# P07_SHARED_SENSORS.net
KiCad netlist of a schematic drawn in EasyEDA
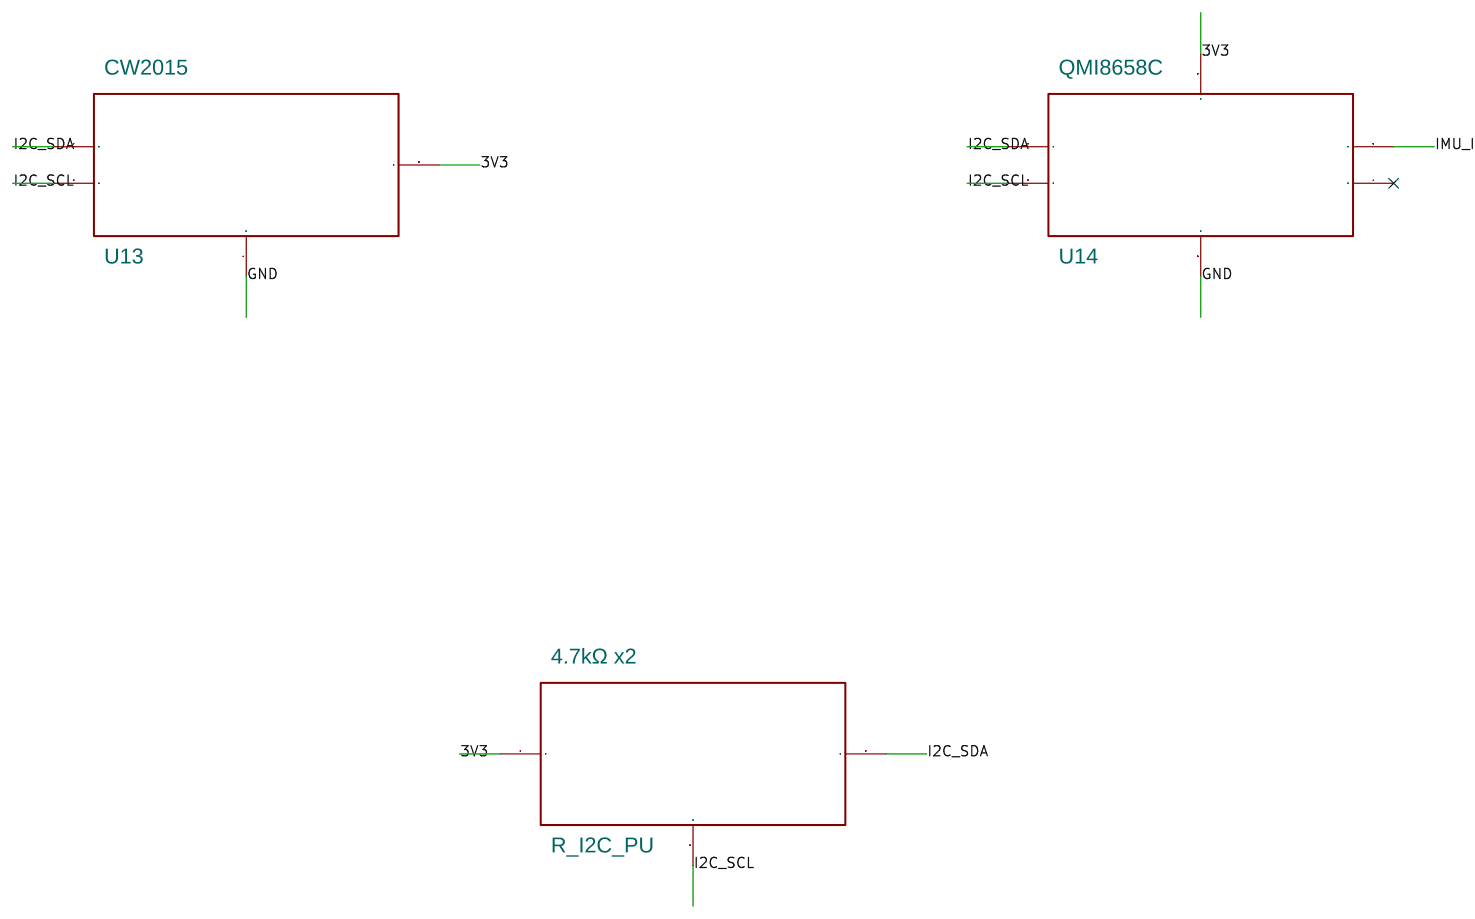
[diagram p0: schematic sheet]

(export (version "E")
  (design (tool "Eeschema 10.0.6"))
  (components
    (comp (ref "R_I2C_PU") (value "4.7kΩ x2") (libsource (lib "") (part "Pullup")))
    (comp (ref "U13") (value "CW2015") (libsource (lib "") (part "Fuel_Gauge")))
    (comp (ref "U14") (value "QMI8658C") (libsource (lib "") (part "QMI8658C")))
  )
  (nets
    (net (code "1") (name "/3V3") (class "Default")
      (node (ref "R_I2C_PU") (pin "1") (pinfunction "1_1") (pintype "unspecified"))
      (node (ref "U13") (pin "3") (pinfunction "1_3") (pintype "unspecified"))
      (node (ref "U14") (pin "5") (pinfunction "1_5") (pintype "unspecified"))
    )
    (net (code "2") (name "/GND") (class "Default")
      (node (ref "U13") (pin "4") (pinfunction "1_4") (pintype "unspecified"))
      (node (ref "U14") (pin "6") (pinfunction "1_6") (pintype "unspecified"))
    )
    (net (code "3") (name "/I2C_SCL") (class "Default")
      (node (ref "R_I2C_PU") (pin "3") (pinfunction "1_3") (pintype "unspecified"))
      (node (ref "U13") (pin "2") (pinfunction "1_2") (pintype "unspecified"))
      (node (ref "U14") (pin "2") (pinfunction "1_2") (pintype "unspecified"))
    )
    (net (code "4") (name "/I2C_SDA") (class "Default")
      (node (ref "R_I2C_PU") (pin "2") (pinfunction "1_2") (pintype "unspecified"))
      (node (ref "U13") (pin "1") (pinfunction "1_1") (pintype "unspecified"))
      (node (ref "U14") (pin "1") (pinfunction "1_1") (pintype "unspecified"))
    )
    (net (code "5") (name "/IMU_INT1") (class "Default")
      (node (ref "U14") (pin "3") (pinfunction "1_3") (pintype "unspecified"))
    )
    (net (code "6") (name "unconnected-(U14-1-Pad4)") (class "Default")
      (node (ref "U14") (pin "4") (pinfunction "1_4") (pintype "unspecified+no_connect"))
    )
  )
)
